# Rover_Sensor_Board.net
KiCad netlist of a schematic drawn in EAGLE
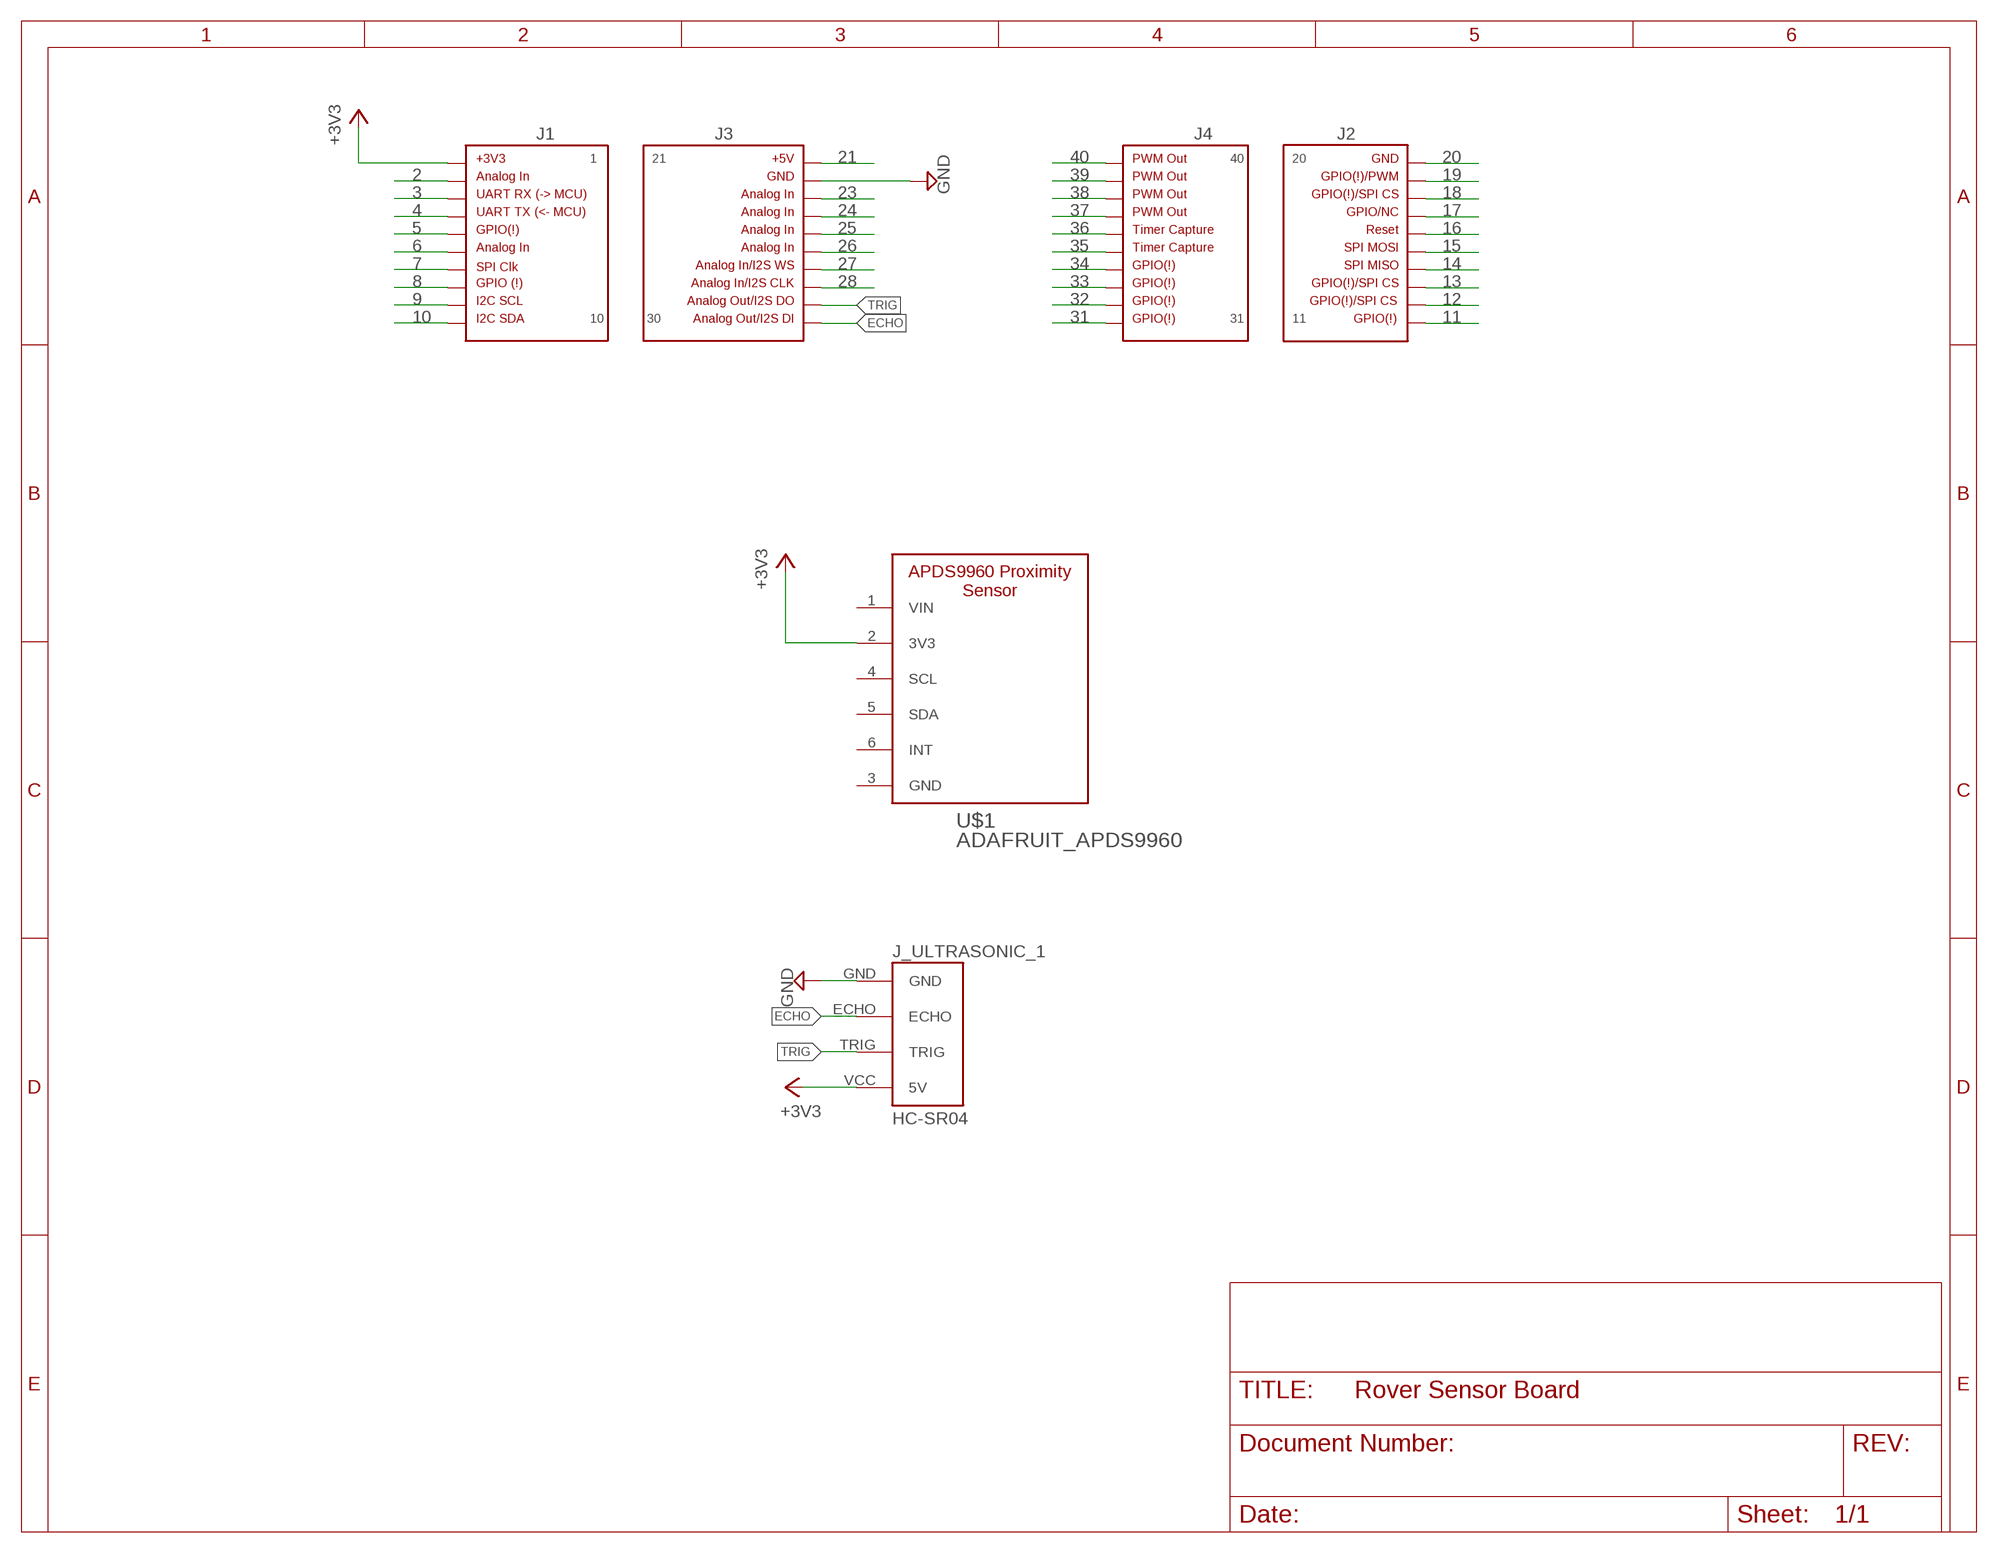
[diagram p0: schematic, sheet 1]

(export (version "E")
  (design (tool "Eeschema 10.0.6"))
  (components
    (comp (ref "J1")
      (value "HEADER1X10-J1SILK_LABELS")
      (footprint "eagle-import:J1")
      (libsource (lib "eagle-import") (part "HEADER1X10-J1SILK_LABELS"))
    )
    (comp (ref "J2")
      (value "HEADER1X10-J2SILK_LABELS")
      (footprint "eagle-import:J2")
      (libsource (lib "eagle-import") (part "HEADER1X10-J2SILK_LABELS"))
    )
    (comp (ref "J3")
      (value "HEADER1X10-J3NOSILK")
      (footprint "eagle-import:1X10-J3")
      (libsource (lib "eagle-import") (part "HEADER1X10-J3NOSILK"))
    )
    (comp (ref "J4")
      (value "HEADER1X10-J4SILK_LABELS")
      (footprint "eagle-import:J4")
      (libsource (lib "eagle-import") (part "HEADER1X10-J4SILK_LABELS"))
    )
    (comp (ref "J_ULTRASONIC_1")
      (value "HC-SR04")
      (footprint "eagle-import:HC-SR04_FOOTPRINT")
      (libsource (lib "eagle-import") (part "HC-SR04"))
    )
    (comp (ref "U$1")
      (value "ADAFRUIT_APDS9960")
      (footprint "eagle-import:ADAFRUIT_APDS9960")
      (libsource (lib "eagle-import") (part "ADAFRUIT_APDS9960"))
    )
  )
  (nets
    (net (code "1") (name "+3V3") (class "Default")
      (node (ref "J1") (pin "1") (pinfunction "1_1") (pintype "bidirectional"))
      (node (ref "J_ULTRASONIC_1") (pin "VCC") (pinfunction "5V_VCC") (pintype "bidirectional"))
      (node (ref "U$1") (pin "2") (pinfunction "3V3_2") (pintype "bidirectional"))
    )
    (net (code "2") (name "/2") (class "Default")
      (node (ref "J1") (pin "2") (pinfunction "2_2") (pintype "bidirectional"))
    )
    (net (code "3") (name "/3") (class "Default")
      (node (ref "J1") (pin "3") (pinfunction "3_3") (pintype "bidirectional"))
    )
    (net (code "4") (name "/4") (class "Default")
      (node (ref "J1") (pin "4") (pinfunction "4_4") (pintype "bidirectional"))
    )
    (net (code "5") (name "/5") (class "Default")
      (node (ref "J1") (pin "5") (pinfunction "5_5") (pintype "bidirectional"))
    )
    (net (code "6") (name "/6") (class "Default")
      (node (ref "J1") (pin "6") (pinfunction "6_6") (pintype "bidirectional"))
    )
    (net (code "7") (name "/7") (class "Default")
      (node (ref "J1") (pin "7") (pinfunction "7_7") (pintype "bidirectional"))
    )
    (net (code "8") (name "/8") (class "Default")
      (node (ref "J1") (pin "8") (pinfunction "8_8") (pintype "bidirectional"))
    )
    (net (code "9") (name "/9") (class "Default")
      (node (ref "J1") (pin "9") (pinfunction "9_9") (pintype "bidirectional"))
    )
    (net (code "10") (name "/10") (class "Default")
      (node (ref "J1") (pin "10") (pinfunction "10_10") (pintype "bidirectional"))
    )
    (net (code "11") (name "/11") (class "Default")
      (node (ref "J2") (pin "11") (pinfunction "11_11") (pintype "bidirectional"))
    )
    (net (code "12") (name "/12") (class "Default")
      (node (ref "J2") (pin "12") (pinfunction "12_12") (pintype "bidirectional"))
    )
    (net (code "13") (name "/13") (class "Default")
      (node (ref "J2") (pin "13") (pinfunction "13_13") (pintype "bidirectional"))
    )
    (net (code "14") (name "/14") (class "Default")
      (node (ref "J2") (pin "14") (pinfunction "14_14") (pintype "bidirectional"))
    )
    (net (code "15") (name "/15") (class "Default")
      (node (ref "J2") (pin "15") (pinfunction "15_15") (pintype "bidirectional"))
    )
    (net (code "16") (name "/16") (class "Default")
      (node (ref "J2") (pin "16") (pinfunction "16_16") (pintype "bidirectional"))
    )
    (net (code "17") (name "/17") (class "Default")
      (node (ref "J2") (pin "17") (pinfunction "17_17") (pintype "bidirectional"))
    )
    (net (code "18") (name "/18") (class "Default")
      (node (ref "J2") (pin "18") (pinfunction "18_18") (pintype "bidirectional"))
    )
    (net (code "19") (name "/19") (class "Default")
      (node (ref "J2") (pin "19") (pinfunction "19_19") (pintype "bidirectional"))
    )
    (net (code "20") (name "/20") (class "Default")
      (node (ref "J2") (pin "20") (pinfunction "20_20") (pintype "bidirectional"))
    )
    (net (code "21") (name "/21") (class "Default")
      (node (ref "J3") (pin "21") (pinfunction "21_21") (pintype "bidirectional"))
    )
    (net (code "22") (name "/23") (class "Default")
      (node (ref "J3") (pin "23") (pinfunction "23_23") (pintype "bidirectional"))
    )
    (net (code "23") (name "/24") (class "Default")
      (node (ref "J3") (pin "24") (pinfunction "24_24") (pintype "bidirectional"))
    )
    (net (code "24") (name "/25") (class "Default")
      (node (ref "J3") (pin "25") (pinfunction "25_25") (pintype "bidirectional"))
    )
    (net (code "25") (name "/26") (class "Default")
      (node (ref "J3") (pin "26") (pinfunction "26_26") (pintype "bidirectional"))
    )
    (net (code "26") (name "/27") (class "Default")
      (node (ref "J3") (pin "27") (pinfunction "27_27") (pintype "bidirectional"))
    )
    (net (code "27") (name "/28") (class "Default")
      (node (ref "J3") (pin "28") (pinfunction "28_28") (pintype "bidirectional"))
    )
    (net (code "28") (name "/31") (class "Default")
      (node (ref "J4") (pin "31") (pinfunction "31_31") (pintype "bidirectional"))
    )
    (net (code "29") (name "/32") (class "Default")
      (node (ref "J4") (pin "32") (pinfunction "32_32") (pintype "bidirectional"))
    )
    (net (code "30") (name "/33") (class "Default")
      (node (ref "J4") (pin "33") (pinfunction "33_33") (pintype "bidirectional"))
    )
    (net (code "31") (name "/34") (class "Default")
      (node (ref "J4") (pin "34") (pinfunction "34_34") (pintype "bidirectional"))
    )
    (net (code "32") (name "/35") (class "Default")
      (node (ref "J4") (pin "35") (pinfunction "35_35") (pintype "bidirectional"))
    )
    (net (code "33") (name "/36") (class "Default")
      (node (ref "J4") (pin "36") (pinfunction "36_36") (pintype "bidirectional"))
    )
    (net (code "34") (name "/37") (class "Default")
      (node (ref "J4") (pin "37") (pinfunction "37_37") (pintype "bidirectional"))
    )
    (net (code "35") (name "/38") (class "Default")
      (node (ref "J4") (pin "38") (pinfunction "38_38") (pintype "bidirectional"))
    )
    (net (code "36") (name "/39") (class "Default")
      (node (ref "J4") (pin "39") (pinfunction "39_39") (pintype "bidirectional"))
    )
    (net (code "37") (name "/40") (class "Default")
      (node (ref "J4") (pin "40") (pinfunction "40_40") (pintype "bidirectional"))
    )
    (net (code "38") (name "ECHO") (class "Default")
      (node (ref "J3") (pin "30") (pinfunction "30_30") (pintype "bidirectional"))
      (node (ref "J_ULTRASONIC_1") (pin "ECHO") (pinfunction "ECHO_ECHO") (pintype "bidirectional"))
    )
    (net (code "39") (name "GND") (class "Default")
      (node (ref "J3") (pin "22") (pinfunction "22_22") (pintype "bidirectional"))
      (node (ref "J_ULTRASONIC_1") (pin "GND") (pinfunction "GND_GND") (pintype "bidirectional"))
    )
    (net (code "40") (name "TRIG") (class "Default")
      (node (ref "J3") (pin "29") (pinfunction "29_29") (pintype "bidirectional"))
      (node (ref "J_ULTRASONIC_1") (pin "TRIG") (pinfunction "TRIG_TRIG") (pintype "bidirectional"))
    )
    (net (code "41") (name "unconnected-(U$1-GND-Pad3)") (class "Default")
      (node (ref "U$1") (pin "3") (pinfunction "GND_3") (pintype "bidirectional"))
    )
    (net (code "42") (name "unconnected-(U$1-INT-Pad6)") (class "Default")
      (node (ref "U$1") (pin "6") (pinfunction "INT_6") (pintype "bidirectional"))
    )
    (net (code "43") (name "unconnected-(U$1-SCL-Pad4)") (class "Default")
      (node (ref "U$1") (pin "4") (pinfunction "SCL_4") (pintype "bidirectional"))
    )
    (net (code "44") (name "unconnected-(U$1-SDA-Pad5)") (class "Default")
      (node (ref "U$1") (pin "5") (pinfunction "SDA_5") (pintype "bidirectional"))
    )
    (net (code "45") (name "unconnected-(U$1-VIN-Pad1)") (class "Default")
      (node (ref "U$1") (pin "1") (pinfunction "VIN_1") (pintype "bidirectional"))
    )
  )
)
